# DCC_mDecoder.net
KiCad netlist of a schematic drawn in EAGLE
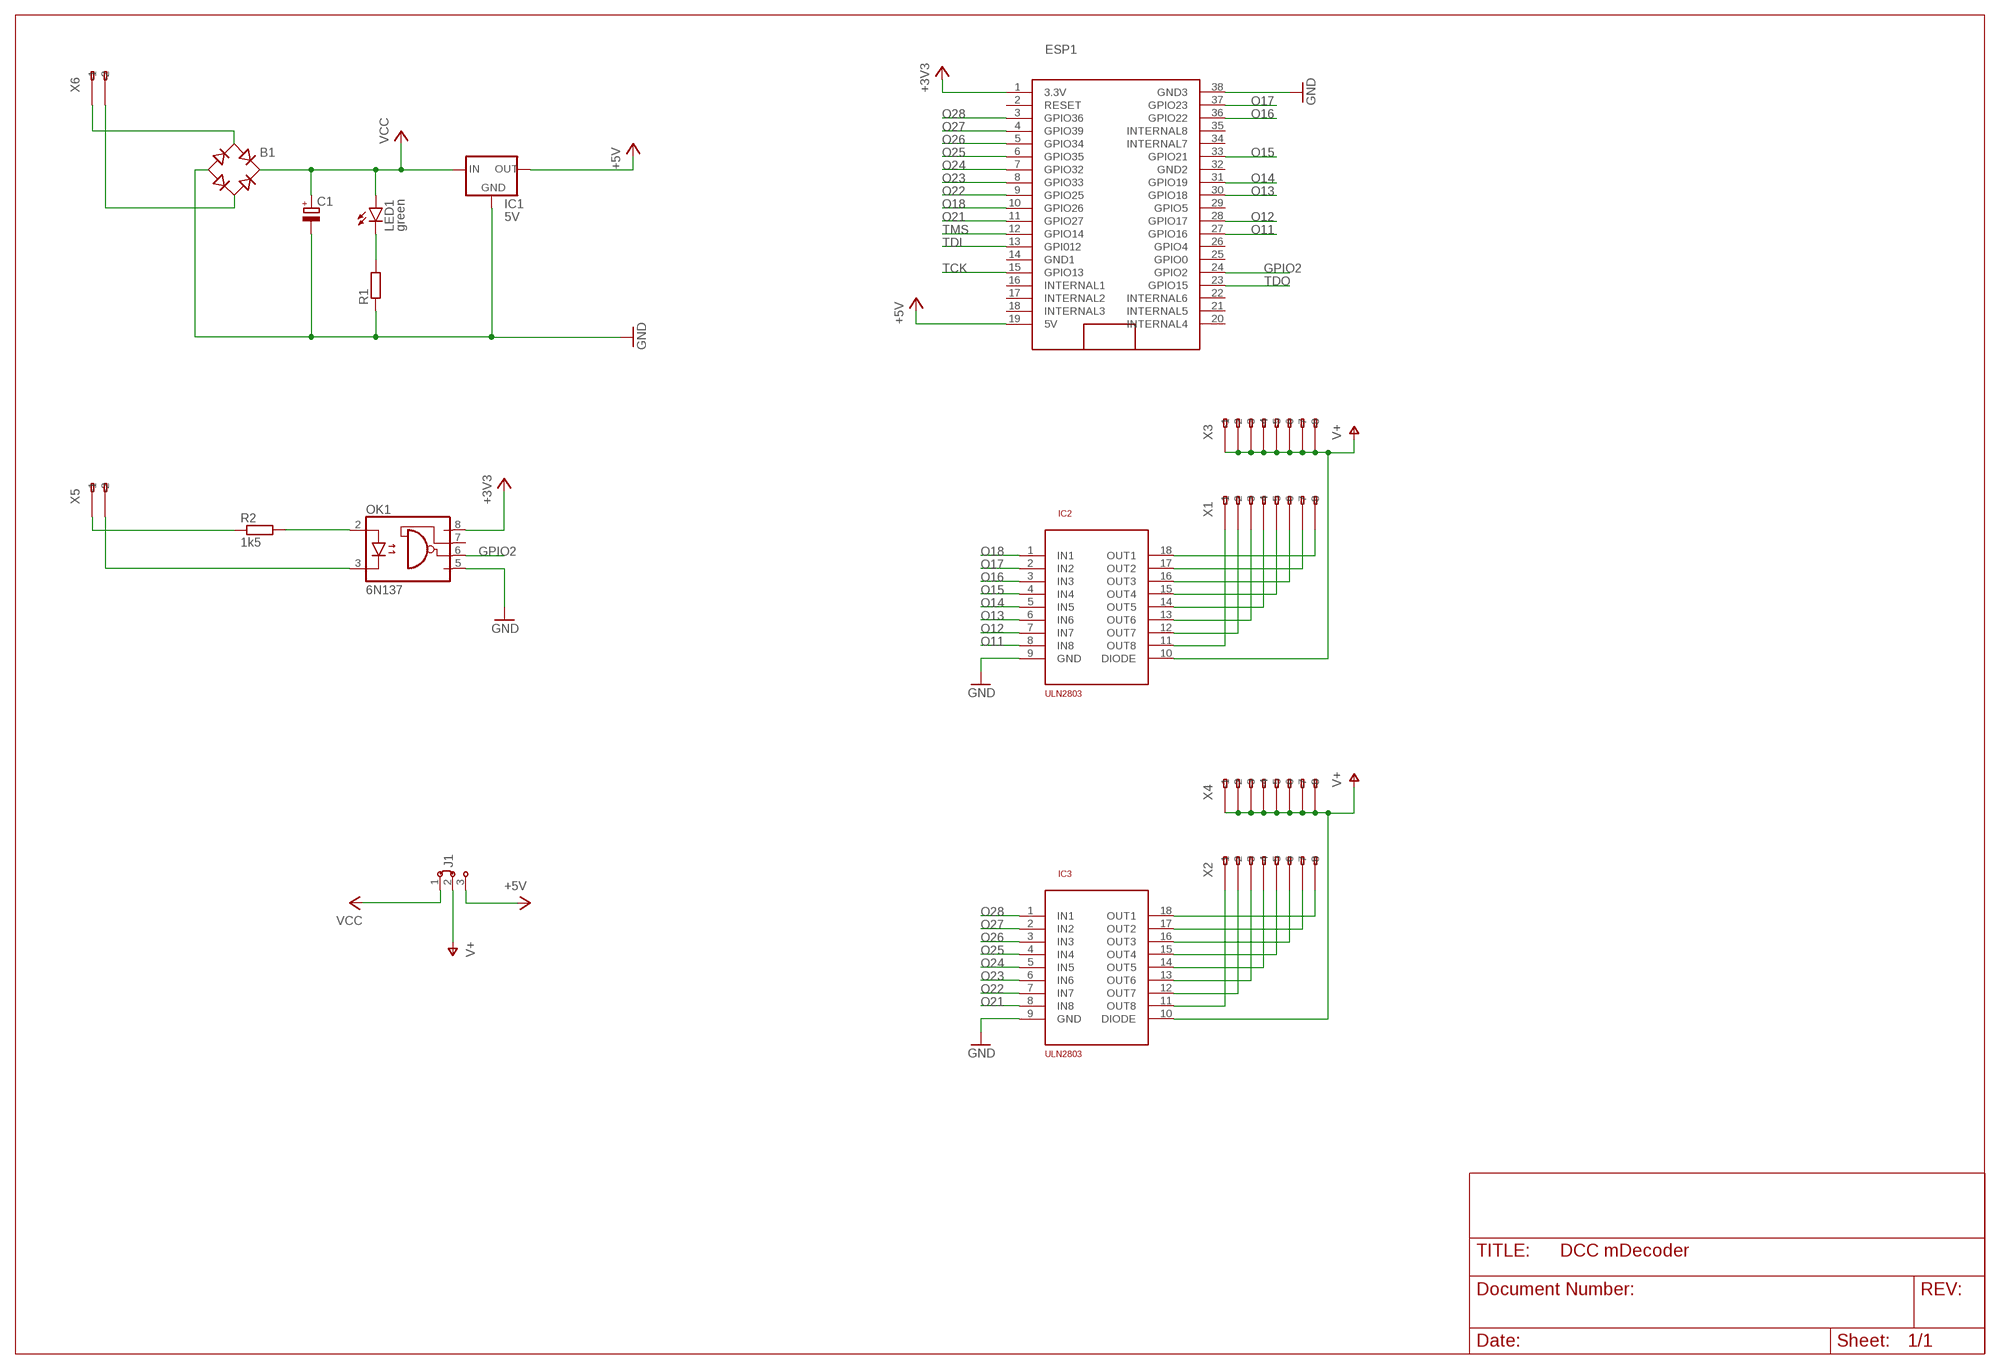
[diagram p0: schematic, sheet 1]

(export (version "E")
  (design (tool "Eeschema 10.0.6"))
  (components
    (comp (ref "B1")
      (value "RB1A")
      (footprint "eagle-import:RB1A")
      (libsource (lib "eagle-import") (part "RB1A"))
    )
    (comp (ref "C1")
      (value "CPOL-EUE5-8.5")
      (footprint "eagle-import:E5-8,5")
      (libsource (lib "eagle-import") (part "CPOL-EUE5-8.5"))
    )
    (comp (ref "ESP1")
      (value "ESP32-NODEMCU")
      (footprint "eagle-import:ESP32_NODEMCU")
      (libsource (lib "eagle-import") (part "ESP32-NODEMCU"))
    )
    (comp (ref "IC1")
      (value "5V")
      (footprint "eagle-import:78XXS")
      (libsource (lib "eagle-import") (part "78XXS"))
    )
    (comp (ref "IC2")
      (value "ULN2803")
      (footprint "eagle-import:DIL18")
      (libsource (lib "eagle-import") (part "ULN2803DIL18"))
    )
    (comp (ref "IC3")
      (value "ULN2803")
      (footprint "eagle-import:DIL18")
      (libsource (lib "eagle-import") (part "ULN2803DIL18"))
    )
    (comp (ref "J1")
      (value "J2X2MM")
      (footprint "eagle-import:04C")
      (libsource (lib "eagle-import") (part "J2X2MM"))
    )
    (comp (ref "LED1")
      (value "green")
      (footprint "eagle-import:LED3MM")
      (fields (field (name "MF") "VISHAY SEMICONDUCTOR"))
      (libsource (lib "eagle-import") (part "TLLG4400"))
    )
    (comp (ref "OK1")
      (value "6N137")
      (footprint "eagle-import:DIL08")
      (libsource (lib "eagle-import") (part "6N137"))
    )
    (comp (ref "R1")
      (value "R-EU_0207/10")
      (footprint "eagle-import:0207_10")
      (libsource (lib "eagle-import") (part "R-EU_0207/10"))
    )
    (comp (ref "R2")
      (value "1k5")
      (footprint "eagle-import:0207_10")
      (libsource (lib "eagle-import") (part "R-EU_0207/10"))
    )
    (comp (ref "X1")
      (value "233-508")
      (footprint "eagle-import:233-508")
      (fields (field (name "MF") "Wago Corporation") (field (name "MPN") "0233-0508"))
      (libsource (lib "eagle-import") (part "233-508"))
    )
    (comp (ref "X2")
      (value "233-508")
      (footprint "eagle-import:233-508")
      (fields (field (name "MF") "Wago Corporation") (field (name "MPN") "0233-0508"))
      (libsource (lib "eagle-import") (part "233-508"))
    )
    (comp (ref "X3")
      (value "233-508")
      (footprint "eagle-import:233-508")
      (fields (field (name "MF") "Wago Corporation") (field (name "MPN") "0233-0508"))
      (libsource (lib "eagle-import") (part "233-508"))
    )
    (comp (ref "X4")
      (value "233-508")
      (footprint "eagle-import:233-508")
      (fields (field (name "MF") "Wago Corporation") (field (name "MPN") "0233-0508"))
      (libsource (lib "eagle-import") (part "233-508"))
    )
    (comp (ref "X5")
      (value "233-202")
      (footprint "eagle-import:233-202")
      (libsource (lib "eagle-import") (part "233-202"))
    )
    (comp (ref "X6")
      (value "233-202")
      (footprint "eagle-import:233-202")
      (libsource (lib "eagle-import") (part "233-202"))
    )
  )
  (nets
    (net (code "1") (name "+3V3") (class "Default")
      (node (ref "ESP1") (pin "1") (pinfunction "3.3V_1") (pintype "power_in"))
      (node (ref "OK1") (pin "8") (pinfunction "VCC_8") (pintype "passive"))
    )
    (net (code "2") (name "+5V") (class "Default")
      (node (ref "ESP1") (pin "19") (pinfunction "5V_19") (pintype "power_in"))
      (node (ref "IC1") (pin "OUT") (pinfunction "OUT_OUT") (pintype "passive"))
      (node (ref "J1") (pin "3") (pinfunction "3_3") (pintype "passive"))
    )
    (net (code "3") (name "/GND1") (class "Default")
      (node (ref "ESP1") (pin "14") (pinfunction "GND1_14") (pintype "power_in"))
    )
    (net (code "4") (name "/GND2") (class "Default")
      (node (ref "ESP1") (pin "32") (pinfunction "GND2_32") (pintype "power_in"))
    )
    (net (code "5") (name "/GPIO2") (class "Default")
      (node (ref "ESP1") (pin "24") (pinfunction "GPIO2_24") (pintype "bidirectional"))
      (node (ref "OK1") (pin "6") (pinfunction "VO_6") (pintype "passive"))
    )
    (net (code "6") (name "/O11") (class "Default")
      (node (ref "ESP1") (pin "27") (pinfunction "GPIO16_27") (pintype "bidirectional"))
      (node (ref "IC2") (pin "8") (pinfunction "IN8_8") (pintype "input"))
    )
    (net (code "7") (name "/O12") (class "Default")
      (node (ref "ESP1") (pin "28") (pinfunction "GPIO17_28") (pintype "bidirectional"))
      (node (ref "IC2") (pin "7") (pinfunction "IN7_7") (pintype "input"))
    )
    (net (code "8") (name "/O13") (class "Default")
      (node (ref "ESP1") (pin "30") (pinfunction "GPIO18_30") (pintype "bidirectional"))
      (node (ref "IC2") (pin "6") (pinfunction "IN6_6") (pintype "input"))
    )
    (net (code "9") (name "/O14") (class "Default")
      (node (ref "ESP1") (pin "31") (pinfunction "GPIO19_31") (pintype "bidirectional"))
      (node (ref "IC2") (pin "5") (pinfunction "IN5_5") (pintype "input"))
    )
    (net (code "10") (name "/O15") (class "Default")
      (node (ref "ESP1") (pin "33") (pinfunction "GPIO21_33") (pintype "bidirectional"))
      (node (ref "IC2") (pin "4") (pinfunction "IN4_4") (pintype "input"))
    )
    (net (code "11") (name "/O16") (class "Default")
      (node (ref "ESP1") (pin "36") (pinfunction "GPIO22_36") (pintype "bidirectional"))
      (node (ref "IC2") (pin "3") (pinfunction "IN3_3") (pintype "input"))
    )
    (net (code "12") (name "/O17") (class "Default")
      (node (ref "ESP1") (pin "37") (pinfunction "GPIO23_37") (pintype "bidirectional"))
      (node (ref "IC2") (pin "2") (pinfunction "IN2_2") (pintype "input"))
    )
    (net (code "13") (name "/O18") (class "Default")
      (node (ref "ESP1") (pin "10") (pinfunction "GPIO26_10") (pintype "bidirectional"))
      (node (ref "IC2") (pin "1") (pinfunction "IN1_1") (pintype "input"))
    )
    (net (code "14") (name "/O21") (class "Default")
      (node (ref "ESP1") (pin "11") (pinfunction "GPIO27_11") (pintype "bidirectional"))
      (node (ref "IC3") (pin "8") (pinfunction "IN8_8") (pintype "input"))
    )
    (net (code "15") (name "/O22") (class "Default")
      (node (ref "ESP1") (pin "9") (pinfunction "GPIO25_9") (pintype "bidirectional"))
      (node (ref "IC3") (pin "7") (pinfunction "IN7_7") (pintype "input"))
    )
    (net (code "16") (name "/O23") (class "Default")
      (node (ref "ESP1") (pin "8") (pinfunction "GPIO33_8") (pintype "bidirectional"))
      (node (ref "IC3") (pin "6") (pinfunction "IN6_6") (pintype "input"))
    )
    (net (code "17") (name "/O24") (class "Default")
      (node (ref "ESP1") (pin "7") (pinfunction "GPIO32_7") (pintype "bidirectional"))
      (node (ref "IC3") (pin "5") (pinfunction "IN5_5") (pintype "input"))
    )
    (net (code "18") (name "/O25") (class "Default")
      (node (ref "ESP1") (pin "6") (pinfunction "GPIO35_6") (pintype "input"))
      (node (ref "IC3") (pin "4") (pinfunction "IN4_4") (pintype "input"))
    )
    (net (code "19") (name "/O26") (class "Default")
      (node (ref "ESP1") (pin "5") (pinfunction "GPIO34_5") (pintype "input"))
      (node (ref "IC3") (pin "3") (pinfunction "IN3_3") (pintype "input"))
    )
    (net (code "20") (name "/O27") (class "Default")
      (node (ref "ESP1") (pin "4") (pinfunction "GPIO39_4") (pintype "input"))
      (node (ref "IC3") (pin "2") (pinfunction "IN2_2") (pintype "input"))
    )
    (net (code "21") (name "/O28") (class "Default")
      (node (ref "ESP1") (pin "3") (pinfunction "GPIO36_3") (pintype "input"))
      (node (ref "IC3") (pin "1") (pinfunction "IN1_1") (pintype "input"))
    )
    (net (code "22") (name "/TCK") (class "Default")
      (node (ref "ESP1") (pin "15") (pinfunction "GPIO13_15") (pintype "bidirectional"))
    )
    (net (code "23") (name "/TDI") (class "Default")
      (node (ref "ESP1") (pin "13") (pinfunction "GPI012_13") (pintype "bidirectional"))
    )
    (net (code "24") (name "/TDO") (class "Default")
      (node (ref "ESP1") (pin "23") (pinfunction "GPIO15_23") (pintype "bidirectional"))
    )
    (net (code "25") (name "/TMS") (class "Default")
      (node (ref "ESP1") (pin "12") (pinfunction "GPIO14_12") (pintype "bidirectional"))
    )
    (net (code "26") (name "GND") (class "Default")
      (node (ref "B1") (pin "-") (pinfunction "-_-") (pintype "passive"))
      (node (ref "C1") (pin "-") (pinfunction "-_-") (pintype "passive"))
      (node (ref "ESP1") (pin "38") (pinfunction "GND3_38") (pintype "power_in"))
      (node (ref "IC1") (pin "GND") (pinfunction "GND_GND") (pintype "input"))
      (node (ref "IC2") (pin "9") (pinfunction "GND_9") (pintype "power_in"))
      (node (ref "IC3") (pin "9") (pinfunction "GND_9") (pintype "power_in"))
      (node (ref "OK1") (pin "5") (pinfunction "GND_5") (pintype "passive"))
      (node (ref "R1") (pin "1") (pinfunction "1_1") (pintype "passive"))
    )
    (net (code "27") (name "Net-(IC2-OUT1)") (class "Default")
      (node (ref "IC2") (pin "18") (pinfunction "OUT1_18") (pintype "open_collector"))
      (node (ref "X1") (pin "A8") (pinfunction "-8_A8") (pintype "passive"))
    )
    (net (code "28") (name "Net-(IC2-OUT2)") (class "Default")
      (node (ref "IC2") (pin "17") (pinfunction "OUT2_17") (pintype "open_collector"))
      (node (ref "X1") (pin "A7") (pinfunction "-7_A7") (pintype "passive"))
    )
    (net (code "29") (name "Net-(IC2-OUT3)") (class "Default")
      (node (ref "IC2") (pin "16") (pinfunction "OUT3_16") (pintype "open_collector"))
      (node (ref "X1") (pin "A6") (pinfunction "-6_A6") (pintype "passive"))
    )
    (net (code "30") (name "Net-(IC2-OUT4)") (class "Default")
      (node (ref "IC2") (pin "15") (pinfunction "OUT4_15") (pintype "open_collector"))
      (node (ref "X1") (pin "A5") (pinfunction "-5_A5") (pintype "passive"))
    )
    (net (code "31") (name "Net-(IC2-OUT5)") (class "Default")
      (node (ref "IC2") (pin "14") (pinfunction "OUT5_14") (pintype "open_collector"))
      (node (ref "X1") (pin "A4") (pinfunction "-4_A4") (pintype "passive"))
    )
    (net (code "32") (name "Net-(IC2-OUT6)") (class "Default")
      (node (ref "IC2") (pin "13") (pinfunction "OUT6_13") (pintype "open_collector"))
      (node (ref "X1") (pin "A3") (pinfunction "-3_A3") (pintype "passive"))
    )
    (net (code "33") (name "Net-(IC2-OUT7)") (class "Default")
      (node (ref "IC2") (pin "12") (pinfunction "OUT7_12") (pintype "open_collector"))
      (node (ref "X1") (pin "A2") (pinfunction "-2_A2") (pintype "passive"))
    )
    (net (code "34") (name "Net-(IC2-OUT8)") (class "Default")
      (node (ref "IC2") (pin "11") (pinfunction "OUT8_11") (pintype "open_collector"))
      (node (ref "X1") (pin "A1") (pinfunction "-1_A1") (pintype "passive"))
    )
    (net (code "35") (name "Net-(IC3-OUT1)") (class "Default")
      (node (ref "IC3") (pin "18") (pinfunction "OUT1_18") (pintype "open_collector"))
      (node (ref "X2") (pin "A8") (pinfunction "-8_A8") (pintype "passive"))
    )
    (net (code "36") (name "Net-(IC3-OUT2)") (class "Default")
      (node (ref "IC3") (pin "17") (pinfunction "OUT2_17") (pintype "open_collector"))
      (node (ref "X2") (pin "A7") (pinfunction "-7_A7") (pintype "passive"))
    )
    (net (code "37") (name "Net-(IC3-OUT3)") (class "Default")
      (node (ref "IC3") (pin "16") (pinfunction "OUT3_16") (pintype "open_collector"))
      (node (ref "X2") (pin "A6") (pinfunction "-6_A6") (pintype "passive"))
    )
    (net (code "38") (name "Net-(IC3-OUT4)") (class "Default")
      (node (ref "IC3") (pin "15") (pinfunction "OUT4_15") (pintype "open_collector"))
      (node (ref "X2") (pin "A5") (pinfunction "-5_A5") (pintype "passive"))
    )
    (net (code "39") (name "Net-(IC3-OUT5)") (class "Default")
      (node (ref "IC3") (pin "14") (pinfunction "OUT5_14") (pintype "open_collector"))
      (node (ref "X2") (pin "A4") (pinfunction "-4_A4") (pintype "passive"))
    )
    (net (code "40") (name "Net-(IC3-OUT6)") (class "Default")
      (node (ref "IC3") (pin "13") (pinfunction "OUT6_13") (pintype "open_collector"))
      (node (ref "X2") (pin "A3") (pinfunction "-3_A3") (pintype "passive"))
    )
    (net (code "41") (name "Net-(IC3-OUT7)") (class "Default")
      (node (ref "IC3") (pin "12") (pinfunction "OUT7_12") (pintype "open_collector"))
      (node (ref "X2") (pin "A2") (pinfunction "-2_A2") (pintype "passive"))
    )
    (net (code "42") (name "Net-(IC3-OUT8)") (class "Default")
      (node (ref "IC3") (pin "11") (pinfunction "OUT8_11") (pintype "open_collector"))
      (node (ref "X2") (pin "A1") (pinfunction "-1_A1") (pintype "passive"))
    )
    (net (code "43") (name "Net-(LED1-C)") (class "Default")
      (node (ref "LED1") (pin "K") (pinfunction "C_K") (pintype "passive"))
      (node (ref "R1") (pin "2") (pinfunction "2_2") (pintype "passive"))
    )
    (net (code "44") (name "Net-(OK1-A)") (class "Default")
      (node (ref "OK1") (pin "2") (pinfunction "A_2") (pintype "passive"))
      (node (ref "R2") (pin "2") (pinfunction "2_2") (pintype "passive"))
    )
    (net (code "45") (name "Net-(OK1-C)") (class "Default")
      (node (ref "OK1") (pin "3") (pinfunction "C_3") (pintype "passive"))
      (node (ref "X5") (pin "A2") (pinfunction "-2_A2") (pintype "passive"))
    )
    (net (code "46") (name "Net-(X5--1)") (class "Default")
      (node (ref "R2") (pin "1") (pinfunction "1_1") (pintype "passive"))
      (node (ref "X5") (pin "A1") (pinfunction "-1_A1") (pintype "passive"))
    )
    (net (code "47") (name "Net-(X6--1)") (class "Default")
      (node (ref "B1") (pin "AC1") (pinfunction "AC1_AC1") (pintype "passive"))
      (node (ref "X6") (pin "A1") (pinfunction "-1_A1") (pintype "passive"))
    )
    (net (code "48") (name "Net-(X6--2)") (class "Default")
      (node (ref "B1") (pin "AC2") (pinfunction "AC2_AC2") (pintype "passive"))
      (node (ref "X6") (pin "A2") (pinfunction "-2_A2") (pintype "passive"))
    )
    (net (code "49") (name "V+") (class "Default")
      (node (ref "IC2") (pin "10") (pinfunction "DIODE_10") (pintype "power_in"))
      (node (ref "IC3") (pin "10") (pinfunction "DIODE_10") (pintype "power_in"))
      (node (ref "J1") (pin "2") (pinfunction "2_2") (pintype "passive"))
      (node (ref "X3") (pin "A1") (pinfunction "-1_A1") (pintype "passive"))
      (node (ref "X3") (pin "A2") (pinfunction "-2_A2") (pintype "passive"))
      (node (ref "X3") (pin "A3") (pinfunction "-3_A3") (pintype "passive"))
      (node (ref "X3") (pin "A4") (pinfunction "-4_A4") (pintype "passive"))
      (node (ref "X3") (pin "A5") (pinfunction "-5_A5") (pintype "passive"))
      (node (ref "X3") (pin "A6") (pinfunction "-6_A6") (pintype "passive"))
      (node (ref "X3") (pin "A7") (pinfunction "-7_A7") (pintype "passive"))
      (node (ref "X3") (pin "A8") (pinfunction "-8_A8") (pintype "passive"))
      (node (ref "X4") (pin "A1") (pinfunction "-1_A1") (pintype "passive"))
      (node (ref "X4") (pin "A2") (pinfunction "-2_A2") (pintype "passive"))
      (node (ref "X4") (pin "A3") (pinfunction "-3_A3") (pintype "passive"))
      (node (ref "X4") (pin "A4") (pinfunction "-4_A4") (pintype "passive"))
      (node (ref "X4") (pin "A5") (pinfunction "-5_A5") (pintype "passive"))
      (node (ref "X4") (pin "A6") (pinfunction "-6_A6") (pintype "passive"))
      (node (ref "X4") (pin "A7") (pinfunction "-7_A7") (pintype "passive"))
      (node (ref "X4") (pin "A8") (pinfunction "-8_A8") (pintype "passive"))
    )
    (net (code "50") (name "VCC") (class "Default")
      (node (ref "B1") (pin "+") (pinfunction "+_+") (pintype "passive"))
      (node (ref "C1") (pin "+") (pinfunction "+_+") (pintype "passive"))
      (node (ref "IC1") (pin "IN") (pinfunction "IN_IN") (pintype "input"))
      (node (ref "J1") (pin "1") (pinfunction "1_1") (pintype "passive"))
      (node (ref "LED1") (pin "A") (pinfunction "A_A") (pintype "passive"))
    )
    (net (code "51") (name "unconnected-(ESP1-GPIO0-Pad25)") (class "Default")
      (node (ref "ESP1") (pin "25") (pinfunction "GPIO0_25") (pintype "output"))
    )
    (net (code "52") (name "unconnected-(ESP1-GPIO4-Pad26)") (class "Default")
      (node (ref "ESP1") (pin "26") (pinfunction "GPIO4_26") (pintype "bidirectional"))
    )
    (net (code "53") (name "unconnected-(ESP1-GPIO5-Pad29)") (class "Default")
      (node (ref "ESP1") (pin "29") (pinfunction "GPIO5_29") (pintype "bidirectional"))
    )
    (net (code "54") (name "unconnected-(ESP1-INTERNAL1-Pad16)") (class "Default")
      (node (ref "ESP1") (pin "16") (pinfunction "INTERNAL1_16") (pintype "no_connect"))
    )
    (net (code "55") (name "unconnected-(ESP1-INTERNAL2-Pad17)") (class "Default")
      (node (ref "ESP1") (pin "17") (pinfunction "INTERNAL2_17") (pintype "no_connect"))
    )
    (net (code "56") (name "unconnected-(ESP1-INTERNAL3-Pad18)") (class "Default")
      (node (ref "ESP1") (pin "18") (pinfunction "INTERNAL3_18") (pintype "no_connect"))
    )
    (net (code "57") (name "unconnected-(ESP1-INTERNAL4-Pad20)") (class "Default")
      (node (ref "ESP1") (pin "20") (pinfunction "INTERNAL4_20") (pintype "no_connect"))
    )
    (net (code "58") (name "unconnected-(ESP1-INTERNAL5-Pad21)") (class "Default")
      (node (ref "ESP1") (pin "21") (pinfunction "INTERNAL5_21") (pintype "no_connect"))
    )
    (net (code "59") (name "unconnected-(ESP1-INTERNAL6-Pad22)") (class "Default")
      (node (ref "ESP1") (pin "22") (pinfunction "INTERNAL6_22") (pintype "no_connect"))
    )
    (net (code "60") (name "unconnected-(ESP1-INTERNAL7-Pad34)") (class "Default")
      (node (ref "ESP1") (pin "34") (pinfunction "INTERNAL7_34") (pintype "no_connect"))
    )
    (net (code "61") (name "unconnected-(ESP1-INTERNAL8-Pad35)") (class "Default")
      (node (ref "ESP1") (pin "35") (pinfunction "INTERNAL8_35") (pintype "no_connect"))
    )
    (net (code "62") (name "unconnected-(ESP1-RESET-Pad2)") (class "Default")
      (node (ref "ESP1") (pin "2") (pinfunction "RESET_2") (pintype "input"))
    )
    (net (code "63") (name "unconnected-(OK1-VE-Pad7)") (class "Default")
      (node (ref "OK1") (pin "7") (pinfunction "VE_7") (pintype "passive"))
    )
    (net (code "64") (name "unconnected-(X1-B-1-PadB1)") (class "Default")
      (node (ref "X1") (pin "B1") (pinfunction "B-1_B1") (pintype "passive"))
    )
    (net (code "65") (name "unconnected-(X1-B-2-PadB2)") (class "Default")
      (node (ref "X1") (pin "B2") (pinfunction "B-2_B2") (pintype "passive"))
    )
    (net (code "66") (name "unconnected-(X1-B-3-PadB3)") (class "Default")
      (node (ref "X1") (pin "B3") (pinfunction "B-3_B3") (pintype "passive"))
    )
    (net (code "67") (name "unconnected-(X1-B-4-PadB4)") (class "Default")
      (node (ref "X1") (pin "B4") (pinfunction "B-4_B4") (pintype "passive"))
    )
    (net (code "68") (name "unconnected-(X1-B-5-PadB5)") (class "Default")
      (node (ref "X1") (pin "B5") (pinfunction "B-5_B5") (pintype "passive"))
    )
    (net (code "69") (name "unconnected-(X1-B-6-PadB6)") (class "Default")
      (node (ref "X1") (pin "B6") (pinfunction "B-6_B6") (pintype "passive"))
    )
    (net (code "70") (name "unconnected-(X1-B-7-PadB7)") (class "Default")
      (node (ref "X1") (pin "B7") (pinfunction "B-7_B7") (pintype "passive"))
    )
    (net (code "71") (name "unconnected-(X1-B-8-PadB8)") (class "Default")
      (node (ref "X1") (pin "B8") (pinfunction "B-8_B8") (pintype "passive"))
    )
    (net (code "72") (name "unconnected-(X2-B-1-PadB1)") (class "Default")
      (node (ref "X2") (pin "B1") (pinfunction "B-1_B1") (pintype "passive"))
    )
    (net (code "73") (name "unconnected-(X2-B-2-PadB2)") (class "Default")
      (node (ref "X2") (pin "B2") (pinfunction "B-2_B2") (pintype "passive"))
    )
    (net (code "74") (name "unconnected-(X2-B-3-PadB3)") (class "Default")
      (node (ref "X2") (pin "B3") (pinfunction "B-3_B3") (pintype "passive"))
    )
    (net (code "75") (name "unconnected-(X2-B-4-PadB4)") (class "Default")
      (node (ref "X2") (pin "B4") (pinfunction "B-4_B4") (pintype "passive"))
    )
    (net (code "76") (name "unconnected-(X2-B-5-PadB5)") (class "Default")
      (node (ref "X2") (pin "B5") (pinfunction "B-5_B5") (pintype "passive"))
    )
    (net (code "77") (name "unconnected-(X2-B-6-PadB6)") (class "Default")
      (node (ref "X2") (pin "B6") (pinfunction "B-6_B6") (pintype "passive"))
    )
    (net (code "78") (name "unconnected-(X2-B-7-PadB7)") (class "Default")
      (node (ref "X2") (pin "B7") (pinfunction "B-7_B7") (pintype "passive"))
    )
    (net (code "79") (name "unconnected-(X2-B-8-PadB8)") (class "Default")
      (node (ref "X2") (pin "B8") (pinfunction "B-8_B8") (pintype "passive"))
    )
    (net (code "80") (name "unconnected-(X3-B-1-PadB1)") (class "Default")
      (node (ref "X3") (pin "B1") (pinfunction "B-1_B1") (pintype "passive"))
    )
    (net (code "81") (name "unconnected-(X3-B-2-PadB2)") (class "Default")
      (node (ref "X3") (pin "B2") (pinfunction "B-2_B2") (pintype "passive"))
    )
    (net (code "82") (name "unconnected-(X3-B-3-PadB3)") (class "Default")
      (node (ref "X3") (pin "B3") (pinfunction "B-3_B3") (pintype "passive"))
    )
    (net (code "83") (name "unconnected-(X3-B-4-PadB4)") (class "Default")
      (node (ref "X3") (pin "B4") (pinfunction "B-4_B4") (pintype "passive"))
    )
    (net (code "84") (name "unconnected-(X3-B-5-PadB5)") (class "Default")
      (node (ref "X3") (pin "B5") (pinfunction "B-5_B5") (pintype "passive"))
    )
    (net (code "85") (name "unconnected-(X3-B-6-PadB6)") (class "Default")
      (node (ref "X3") (pin "B6") (pinfunction "B-6_B6") (pintype "passive"))
    )
    (net (code "86") (name "unconnected-(X3-B-7-PadB7)") (class "Default")
      (node (ref "X3") (pin "B7") (pinfunction "B-7_B7") (pintype "passive"))
    )
    (net (code "87") (name "unconnected-(X3-B-8-PadB8)") (class "Default")
      (node (ref "X3") (pin "B8") (pinfunction "B-8_B8") (pintype "passive"))
    )
    (net (code "88") (name "unconnected-(X4-B-1-PadB1)") (class "Default")
      (node (ref "X4") (pin "B1") (pinfunction "B-1_B1") (pintype "passive"))
    )
    (net (code "89") (name "unconnected-(X4-B-2-PadB2)") (class "Default")
      (node (ref "X4") (pin "B2") (pinfunction "B-2_B2") (pintype "passive"))
    )
    (net (code "90") (name "unconnected-(X4-B-3-PadB3)") (class "Default")
      (node (ref "X4") (pin "B3") (pinfunction "B-3_B3") (pintype "passive"))
    )
    (net (code "91") (name "unconnected-(X4-B-4-PadB4)") (class "Default")
      (node (ref "X4") (pin "B4") (pinfunction "B-4_B4") (pintype "passive"))
    )
    (net (code "92") (name "unconnected-(X4-B-5-PadB5)") (class "Default")
      (node (ref "X4") (pin "B5") (pinfunction "B-5_B5") (pintype "passive"))
    )
    (net (code "93") (name "unconnected-(X4-B-6-PadB6)") (class "Default")
      (node (ref "X4") (pin "B6") (pinfunction "B-6_B6") (pintype "passive"))
    )
    (net (code "94") (name "unconnected-(X4-B-7-PadB7)") (class "Default")
      (node (ref "X4") (pin "B7") (pinfunction "B-7_B7") (pintype "passive"))
    )
    (net (code "95") (name "unconnected-(X4-B-8-PadB8)") (class "Default")
      (node (ref "X4") (pin "B8") (pinfunction "B-8_B8") (pintype "passive"))
    )
    (net (code "96") (name "unconnected-(X5-B-1-PadB1)") (class "Default")
      (node (ref "X5") (pin "B1") (pinfunction "B-1_B1") (pintype "passive"))
    )
    (net (code "97") (name "unconnected-(X5-B-2-PadB2)") (class "Default")
      (node (ref "X5") (pin "B2") (pinfunction "B-2_B2") (pintype "passive"))
    )
    (net (code "98") (name "unconnected-(X6-B-1-PadB1)") (class "Default")
      (node (ref "X6") (pin "B1") (pinfunction "B-1_B1") (pintype "passive"))
    )
    (net (code "99") (name "unconnected-(X6-B-2-PadB2)") (class "Default")
      (node (ref "X6") (pin "B2") (pinfunction "B-2_B2") (pintype "passive"))
    )
  )
)
